# E-inkV0_9.net
KiCad netlist of a schematic drawn in EAGLE
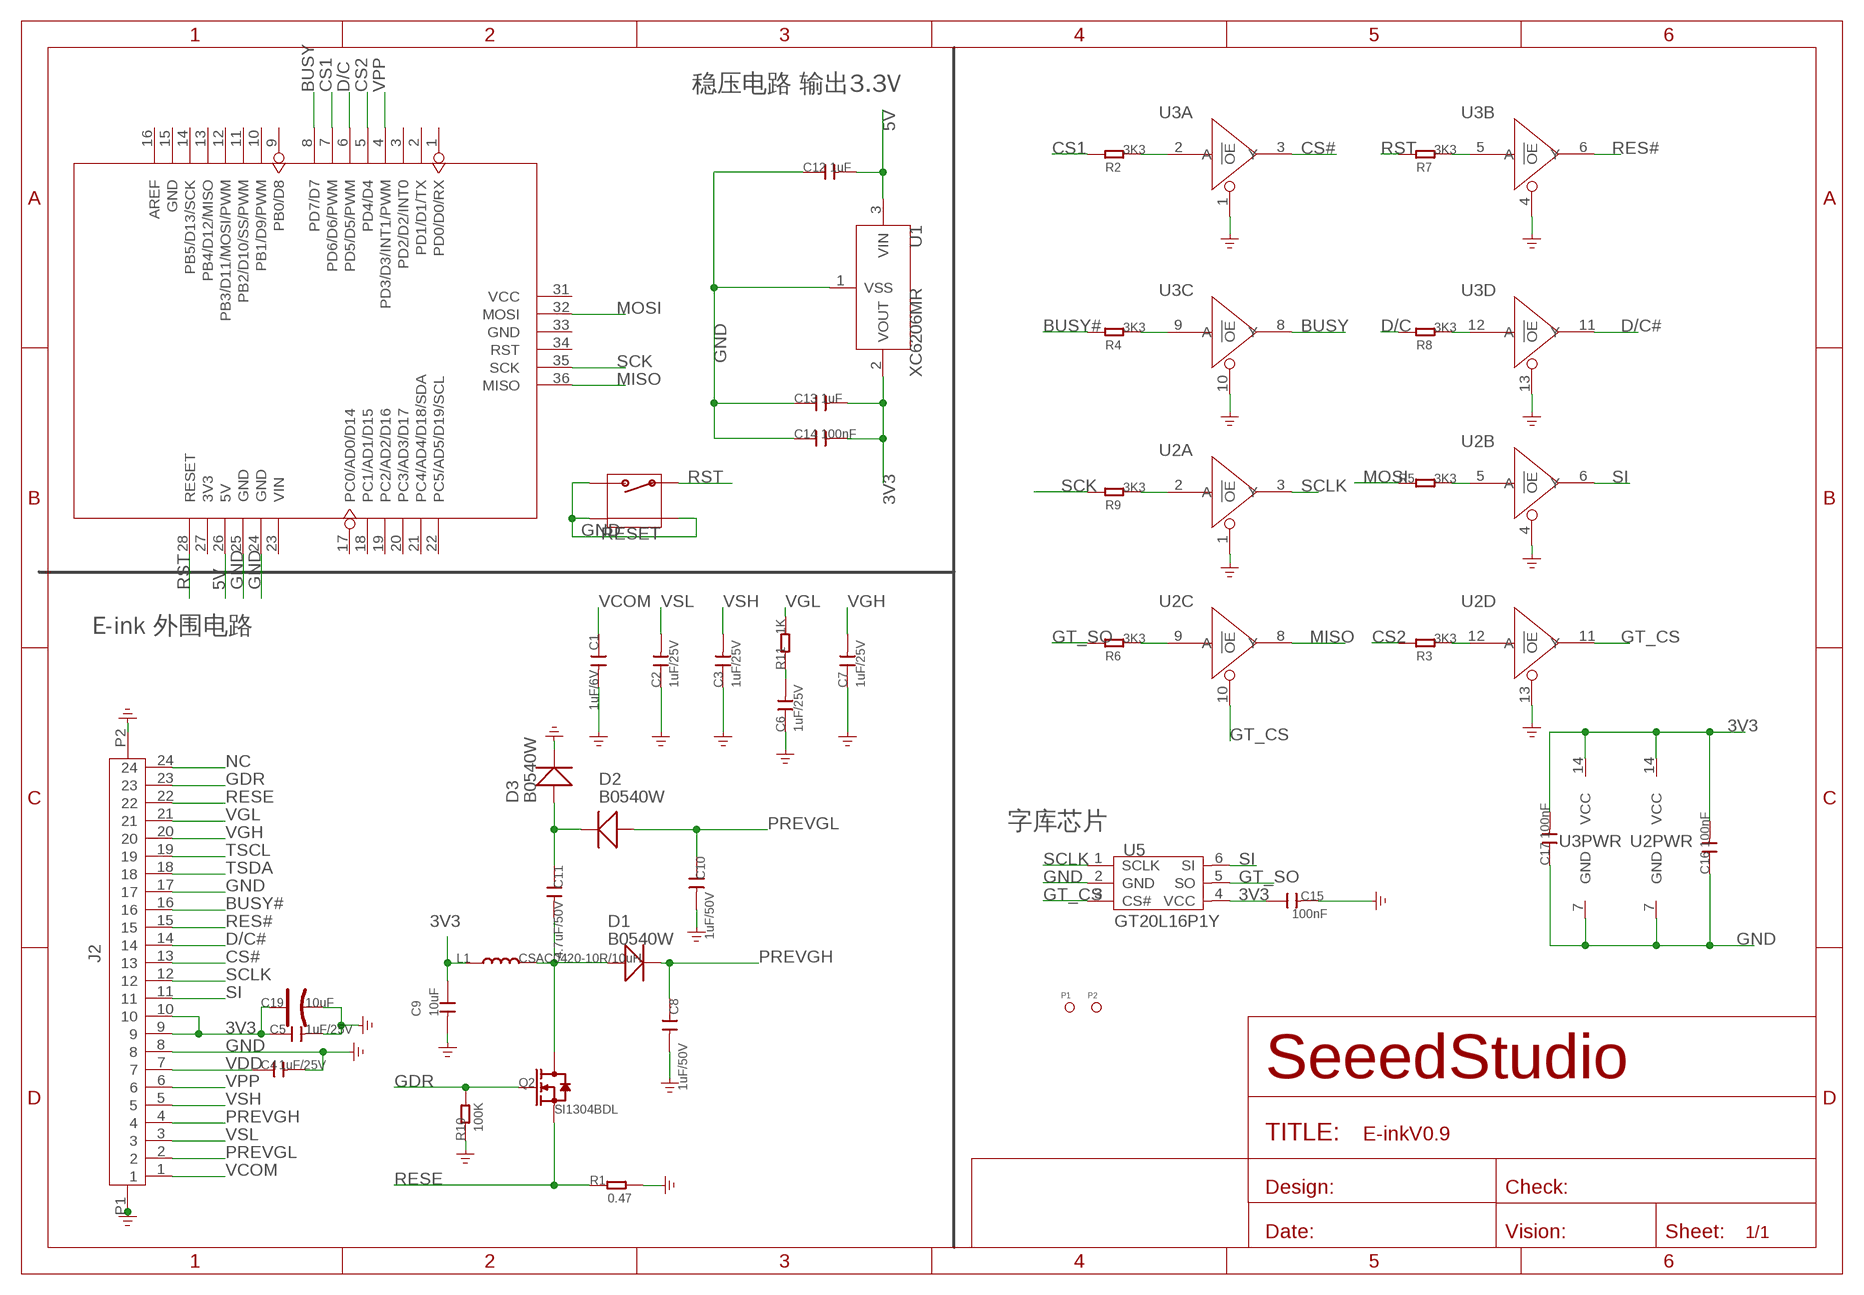
[diagram p0: schematic, sheet 1]

(export (version "E")
  (design (tool "Eeschema 10.0.6"))
  (components
    (comp (ref "C1")
      (value "1uF/6V")
      (footprint "eagle-import:C0805")
      (libsource (lib "eagle-import") (part "C-0805"))
    )
    (comp (ref "C2")
      (value "1uF/25V")
      (footprint "eagle-import:C0805")
      (libsource (lib "eagle-import") (part "C-0805"))
    )
    (comp (ref "C3")
      (value "1uF/25V")
      (footprint "eagle-import:C0805")
      (libsource (lib "eagle-import") (part "C-0805"))
    )
    (comp (ref "C4")
      (value "1uF/25V")
      (footprint "eagle-import:C0805")
      (libsource (lib "eagle-import") (part "C-0805"))
    )
    (comp (ref "C5")
      (value "1uF/25V")
      (footprint "eagle-import:C0805")
      (libsource (lib "eagle-import") (part "C-0805"))
    )
    (comp (ref "C6")
      (value "1uF/25V")
      (footprint "eagle-import:C0805")
      (libsource (lib "eagle-import") (part "C-0805"))
    )
    (comp (ref "C7")
      (value "1uF/25V")
      (footprint "eagle-import:C0805")
      (libsource (lib "eagle-import") (part "C-0805"))
    )
    (comp (ref "C8")
      (value "1uF/50V")
      (footprint "eagle-import:C0805")
      (libsource (lib "eagle-import") (part "C-0805"))
    )
    (comp (ref "C9")
      (value "10uF")
      (footprint "eagle-import:C0805")
      (libsource (lib "eagle-import") (part "C-0805"))
    )
    (comp (ref "C10")
      (value "1uF/50V")
      (footprint "eagle-import:C0805")
      (libsource (lib "eagle-import") (part "C-0805"))
    )
    (comp (ref "C11")
      (value "4.7uF/50V")
      (footprint "eagle-import:C0805")
      (libsource (lib "eagle-import") (part "C-0805"))
    )
    (comp (ref "C12")
      (value "1uF")
      (footprint "eagle-import:C0805")
      (libsource (lib "eagle-import") (part "C-0805"))
    )
    (comp (ref "C13")
      (value "1uF")
      (footprint "eagle-import:C0805")
      (libsource (lib "eagle-import") (part "C-0805"))
    )
    (comp (ref "C14")
      (value "100nF")
      (footprint "eagle-import:C0603")
      (libsource (lib "eagle-import") (part "C-0603"))
    )
    (comp (ref "C15")
      (value "100nF")
      (footprint "eagle-import:C0603")
      (libsource (lib "eagle-import") (part "C-0603"))
    )
    (comp (ref "C16")
      (value "100nF")
      (footprint "eagle-import:C0603")
      (libsource (lib "eagle-import") (part "C-0603"))
    )
    (comp (ref "C17")
      (value "100nF")
      (footprint "eagle-import:C0603")
      (libsource (lib "eagle-import") (part "C-0603"))
    )
    (comp (ref "C19")
      (value "10uF")
      (footprint "eagle-import:AVX-A")
      (libsource (lib "eagle-import") (part "CAP-AVX-A"))
    )
    (comp (ref "D1")
      (value "B0540W")
      (footprint "eagle-import:SOD123-2.7X1.6")
      (libsource (lib "eagle-import") (part "D'MBR0520LT1'"))
    )
    (comp (ref "D2")
      (value "B0540W")
      (footprint "eagle-import:SOD123-2.7X1.6")
      (libsource (lib "eagle-import") (part "D'MBR0520LT1'"))
    )
    (comp (ref "D3")
      (value "B0540W")
      (footprint "eagle-import:SOD123-2.7X1.6")
      (libsource (lib "eagle-import") (part "D'MBR0520LT1'"))
    )
    (comp (ref "J2")
      (value "FPC_CONNECTOR")
      (footprint "eagle-import:24P-0.5")
      (libsource (lib "eagle-import") (part "FPC-CONNECTOR-24P-0.5'ST-FPC-052024-B'"))
    )
    (comp (ref "L1")
      (value "CSAC0420-10R/10uH")
      (footprint "eagle-import:1616BZ")
      (libsource (lib "eagle-import") (part "L'1616BZ'"))
    )
    (comp (ref "P1")
      (value "PAD-MARK")
      (footprint "eagle-import:ROUND-MARK-1.0")
      (fields (field (name "PARTNO") "DNP"))
      (libsource (lib "eagle-import") (part "PAD-MARK"))
    )
    (comp (ref "P2")
      (value "PAD-MARK")
      (footprint "eagle-import:ROUND-MARK-1.0")
      (fields (field (name "PARTNO") "DNP"))
      (libsource (lib "eagle-import") (part "PAD-MARK"))
    )
    (comp (ref "Q2")
      (value "SI1304BDL")
      (footprint "eagle-import:SOT323")
      (libsource (lib "eagle-import") (part "MOSFET-N'SI1304BDL'"))
    )
    (comp (ref "R1")
      (value "0.47")
      (footprint "eagle-import:R0603")
      (libsource (lib "eagle-import") (part "R-0603"))
    )
    (comp (ref "R2")
      (value "3K3")
      (footprint "eagle-import:R0603")
      (libsource (lib "eagle-import") (part "R-0603"))
    )
    (comp (ref "R3")
      (value "3K3")
      (footprint "eagle-import:R0603")
      (libsource (lib "eagle-import") (part "R-0603"))
    )
    (comp (ref "R4")
      (value "3K3")
      (footprint "eagle-import:R0603")
      (libsource (lib "eagle-import") (part "R-0603"))
    )
    (comp (ref "R5")
      (value "3K3")
      (footprint "eagle-import:R0603")
      (libsource (lib "eagle-import") (part "R-0603"))
    )
    (comp (ref "R6")
      (value "3K3")
      (footprint "eagle-import:R0603")
      (libsource (lib "eagle-import") (part "R-0603"))
    )
    (comp (ref "R7")
      (value "3K3")
      (footprint "eagle-import:R0603")
      (libsource (lib "eagle-import") (part "R-0603"))
    )
    (comp (ref "R8")
      (value "3K3")
      (footprint "eagle-import:R0603")
      (libsource (lib "eagle-import") (part "R-0603"))
    )
    (comp (ref "R9")
      (value "3K3")
      (footprint "eagle-import:R0603")
      (libsource (lib "eagle-import") (part "R-0603"))
    )
    (comp (ref "R10")
      (value "100K")
      (footprint "eagle-import:R0603")
      (libsource (lib "eagle-import") (part "R-0603"))
    )
    (comp (ref "R11")
      (value "1K")
      (footprint "eagle-import:R0603")
      (libsource (lib "eagle-import") (part "R-0603"))
    )
    (comp (ref "RESET")
      (value "FOR_TEST_ALBERT_V6_BUTTON_4P_SMD")
      (footprint "eagle-import:FOR_TEST_ALBERT_V6_4P-SMD-7X3.5X3.5")
      (libsource (lib "eagle-import") (part "FOR_TEST_ALBERT_V6_BUTTON_4P_SMD"))
    )
    (comp (ref "U1")
      (value "XC6206MR")
      (footprint "eagle-import:SOT23")
      (libsource (lib "eagle-import") (part "XC6206MR"))
    )
    (comp (ref "U2")
      (value "74VHC125PW")
      (footprint "eagle-import:TSSOP14")
      (libsource (lib "eagle-import") (part "74V125PWHC"))
    )
    (comp (ref "U3")
      (value "74VHC125PW")
      (footprint "eagle-import:TSSOP14")
      (libsource (lib "eagle-import") (part "74V125PWHC"))
    )
    (comp (ref "U4")
      (value "ARDUINO")
      (footprint "eagle-import:ARDUINO-ISP-SMD")
      (libsource (lib "eagle-import") (part "ARDUINO"))
    )
    (comp (ref "U5")
      (value "GT20L16P1Y")
      (footprint "eagle-import:SOT23-6")
      (libsource (lib "eagle-import") (part "GT20L16P1Y"))
    )
  )
  (nets
    (net (code "1") (name "/3V3") (class "Default")
      (node (ref "C13") (pin "2") (pinfunction "2_2") (pintype "passive"))
      (node (ref "C14") (pin "2") (pinfunction "2_2") (pintype "passive"))
      (node (ref "C15") (pin "1") (pinfunction "1_1") (pintype "passive"))
      (node (ref "C16") (pin "2") (pinfunction "2_2") (pintype "passive"))
      (node (ref "C17") (pin "2") (pinfunction "2_2") (pintype "passive"))
      (node (ref "C19") (pin "+") (pinfunction "+_+") (pintype "passive"))
      (node (ref "C5") (pin "1") (pinfunction "1_1") (pintype "passive"))
      (node (ref "C9") (pin "1") (pinfunction "1_1") (pintype "passive"))
      (node (ref "J2") (pin "10") (pinfunction "10_10") (pintype "bidirectional"))
      (node (ref "J2") (pin "9") (pinfunction "9_9") (pintype "bidirectional"))
      (node (ref "L1") (pin "1") (pinfunction "1_1") (pintype "passive"))
      (node (ref "U1") (pin "2") (pinfunction "VOUT_2") (pintype "output"))
      (node (ref "U2") (pin "14") (pinfunction "VCC_14") (pintype "power_in"))
      (node (ref "U3") (pin "14") (pinfunction "VCC_14") (pintype "power_in"))
      (node (ref "U5") (pin "4") (pinfunction "VCC_4") (pintype "power_in"))
    )
    (net (code "2") (name "/5V") (class "Default")
      (node (ref "C12") (pin "2") (pinfunction "2_2") (pintype "passive"))
      (node (ref "U1") (pin "3") (pinfunction "VIN_3") (pintype "input"))
      (node (ref "U4") (pin "26") (pinfunction "5V_26") (pintype "bidirectional"))
    )
    (net (code "3") (name "/BUSY") (class "Default")
      (node (ref "U3") (pin "8") (pinfunction "Y_8") (pintype "bidirectional"))
      (node (ref "U4") (pin "8") (pinfunction "PD7/D7_8") (pintype "bidirectional"))
    )
    (net (code "4") (name "/BUSY#") (class "Default")
      (node (ref "J2") (pin "16") (pinfunction "16_16") (pintype "bidirectional"))
      (node (ref "R4") (pin "1") (pinfunction "1_1") (pintype "passive"))
    )
    (net (code "5") (name "/CS#") (class "Default")
      (node (ref "J2") (pin "13") (pinfunction "13_13") (pintype "bidirectional"))
      (node (ref "U3") (pin "3") (pinfunction "Y_3") (pintype "bidirectional"))
    )
    (net (code "6") (name "/CS1") (class "Default")
      (node (ref "R2") (pin "1") (pinfunction "1_1") (pintype "passive"))
      (node (ref "U4") (pin "7") (pinfunction "PD6/D6/PWM_7") (pintype "bidirectional"))
    )
    (net (code "7") (name "/CS2") (class "Default")
      (node (ref "R3") (pin "1") (pinfunction "1_1") (pintype "passive"))
      (node (ref "U4") (pin "5") (pinfunction "PD4/D4_5") (pintype "bidirectional"))
    )
    (net (code "8") (name "/D{slash}C") (class "Default")
      (node (ref "R8") (pin "1") (pinfunction "1_1") (pintype "passive"))
      (node (ref "U4") (pin "6") (pinfunction "PD5/D5/PWM_6") (pintype "bidirectional"))
    )
    (net (code "9") (name "/D{slash}C#") (class "Default")
      (node (ref "J2") (pin "14") (pinfunction "14_14") (pintype "bidirectional"))
      (node (ref "U3") (pin "11") (pinfunction "Y_11") (pintype "bidirectional"))
    )
    (net (code "10") (name "/GDR") (class "Default")
      (node (ref "J2") (pin "23") (pinfunction "23_23") (pintype "bidirectional"))
      (node (ref "Q2") (pin "1") (pinfunction "G_1") (pintype "passive"))
      (node (ref "R10") (pin "2") (pinfunction "2_2") (pintype "passive"))
    )
    (net (code "11") (name "/GT_CS") (class "Default")
      (node (ref "U2") (pin "10") (pinfunction "~{OE}_10") (pintype "bidirectional"))
      (node (ref "U2") (pin "11") (pinfunction "Y_11") (pintype "bidirectional"))
      (node (ref "U5") (pin "3") (pinfunction "CS#_3") (pintype "input"))
    )
    (net (code "12") (name "/GT_SO") (class "Default")
      (node (ref "R6") (pin "1") (pinfunction "1_1") (pintype "passive"))
      (node (ref "U5") (pin "5") (pinfunction "SO_5") (pintype "output"))
    )
    (net (code "13") (name "/MISO") (class "Default")
      (node (ref "U2") (pin "8") (pinfunction "Y_8") (pintype "bidirectional"))
      (node (ref "U4") (pin "36") (pinfunction "MISO_36") (pintype "bidirectional"))
    )
    (net (code "14") (name "/MOSI") (class "Default")
      (node (ref "R5") (pin "1") (pinfunction "1_1") (pintype "passive"))
      (node (ref "U4") (pin "32") (pinfunction "MOSI_32") (pintype "bidirectional"))
    )
    (net (code "15") (name "/NC") (class "Default")
      (node (ref "J2") (pin "24") (pinfunction "24_24") (pintype "bidirectional"))
    )
    (net (code "16") (name "/PREVGH") (class "Default")
      (node (ref "C8") (pin "1") (pinfunction "1_1") (pintype "passive"))
      (node (ref "D1") (pin "2") (pinfunction "-_2") (pintype "passive"))
      (node (ref "J2") (pin "4") (pinfunction "4_4") (pintype "bidirectional"))
    )
    (net (code "17") (name "/PREVGL") (class "Default")
      (node (ref "C10") (pin "1") (pinfunction "1_1") (pintype "passive"))
      (node (ref "D2") (pin "1") (pinfunction "+_1") (pintype "passive"))
      (node (ref "J2") (pin "2") (pinfunction "2_2") (pintype "bidirectional"))
    )
    (net (code "18") (name "/RES#") (class "Default")
      (node (ref "J2") (pin "15") (pinfunction "15_15") (pintype "bidirectional"))
      (node (ref "U3") (pin "6") (pinfunction "Y_6") (pintype "bidirectional"))
    )
    (net (code "19") (name "/RESE") (class "Default")
      (node (ref "J2") (pin "22") (pinfunction "22_22") (pintype "bidirectional"))
      (node (ref "Q2") (pin "2") (pinfunction "S_2") (pintype "passive"))
      (node (ref "R1") (pin "1") (pinfunction "1_1") (pintype "passive"))
    )
    (net (code "20") (name "/RST") (class "Default")
      (node (ref "R7") (pin "1") (pinfunction "1_1") (pintype "passive"))
      (node (ref "RESET") (pin "1") (pinfunction "1_1") (pintype "bidirectional"))
      (node (ref "U4") (pin "28") (pinfunction "RESET_28") (pintype "bidirectional"))
    )
    (net (code "21") (name "/SCK") (class "Default")
      (node (ref "R9") (pin "1") (pinfunction "1_1") (pintype "passive"))
      (node (ref "U4") (pin "35") (pinfunction "SCK_35") (pintype "bidirectional"))
    )
    (net (code "22") (name "/SCLK") (class "Default")
      (node (ref "J2") (pin "12") (pinfunction "12_12") (pintype "bidirectional"))
      (node (ref "U2") (pin "3") (pinfunction "Y_3") (pintype "bidirectional"))
      (node (ref "U5") (pin "1") (pinfunction "SCLK_1") (pintype "input"))
    )
    (net (code "23") (name "/SI") (class "Default")
      (node (ref "J2") (pin "11") (pinfunction "11_11") (pintype "bidirectional"))
      (node (ref "U2") (pin "6") (pinfunction "Y_6") (pintype "bidirectional"))
      (node (ref "U5") (pin "6") (pinfunction "SI_6") (pintype "input"))
    )
    (net (code "24") (name "/TSCL") (class "Default")
      (node (ref "J2") (pin "19") (pinfunction "19_19") (pintype "bidirectional"))
    )
    (net (code "25") (name "/TSDA") (class "Default")
      (node (ref "J2") (pin "18") (pinfunction "18_18") (pintype "bidirectional"))
    )
    (net (code "26") (name "/VCOM") (class "Default")
      (node (ref "C1") (pin "1") (pinfunction "1_1") (pintype "passive"))
      (node (ref "J2") (pin "1") (pinfunction "1_1") (pintype "bidirectional"))
    )
    (net (code "27") (name "/VDD") (class "Default")
      (node (ref "C4") (pin "1") (pinfunction "1_1") (pintype "passive"))
      (node (ref "J2") (pin "7") (pinfunction "7_7") (pintype "bidirectional"))
    )
    (net (code "28") (name "/VGH") (class "Default")
      (node (ref "C7") (pin "2") (pinfunction "2_2") (pintype "passive"))
      (node (ref "J2") (pin "20") (pinfunction "20_20") (pintype "bidirectional"))
    )
    (net (code "29") (name "/VGL") (class "Default")
      (node (ref "J2") (pin "21") (pinfunction "21_21") (pintype "bidirectional"))
      (node (ref "R11") (pin "2") (pinfunction "2_2") (pintype "passive"))
    )
    (net (code "30") (name "/VPP") (class "Default")
      (node (ref "J2") (pin "6") (pinfunction "6_6") (pintype "bidirectional"))
      (node (ref "U4") (pin "4") (pinfunction "PD3/D3/INT1/PWM_4") (pintype "bidirectional"))
    )
    (net (code "31") (name "/VSH") (class "Default")
      (node (ref "C3") (pin "2") (pinfunction "2_2") (pintype "passive"))
      (node (ref "J2") (pin "5") (pinfunction "5_5") (pintype "bidirectional"))
    )
    (net (code "32") (name "/VSL") (class "Default")
      (node (ref "C2") (pin "2") (pinfunction "2_2") (pintype "passive"))
      (node (ref "J2") (pin "3") (pinfunction "3_3") (pintype "bidirectional"))
    )
    (net (code "33") (name "GND_POWER") (class "Default")
      (node (ref "C1") (pin "2") (pinfunction "2_2") (pintype "passive"))
      (node (ref "C10") (pin "2") (pinfunction "2_2") (pintype "passive"))
      (node (ref "C12") (pin "1") (pinfunction "1_1") (pintype "passive"))
      (node (ref "C13") (pin "1") (pinfunction "1_1") (pintype "passive"))
      (node (ref "C14") (pin "1") (pinfunction "1_1") (pintype "passive"))
      (node (ref "C15") (pin "2") (pinfunction "2_2") (pintype "passive"))
      (node (ref "C16") (pin "1") (pinfunction "1_1") (pintype "passive"))
      (node (ref "C17") (pin "1") (pinfunction "1_1") (pintype "passive"))
      (node (ref "C19") (pin "-") (pinfunction "-_-") (pintype "passive"))
      (node (ref "C2") (pin "1") (pinfunction "1_1") (pintype "passive"))
      (node (ref "C3") (pin "1") (pinfunction "1_1") (pintype "passive"))
      (node (ref "C4") (pin "2") (pinfunction "2_2") (pintype "passive"))
      (node (ref "C5") (pin "2") (pinfunction "2_2") (pintype "passive"))
      (node (ref "C6") (pin "1") (pinfunction "1_1") (pintype "passive"))
      (node (ref "C7") (pin "1") (pinfunction "1_1") (pintype "passive"))
      (node (ref "C8") (pin "2") (pinfunction "2_2") (pintype "passive"))
      (node (ref "C9") (pin "2") (pinfunction "2_2") (pintype "passive"))
      (node (ref "D3") (pin "2") (pinfunction "-_2") (pintype "passive"))
      (node (ref "J2") (pin "17") (pinfunction "17_17") (pintype "bidirectional"))
      (node (ref "J2") (pin "8") (pinfunction "8_8") (pintype "bidirectional"))
      (node (ref "J2") (pin "P1") (pinfunction "P1_P1") (pintype "bidirectional"))
      (node (ref "J2") (pin "P2") (pinfunction "P2_P2") (pintype "bidirectional"))
      (node (ref "R1") (pin "2") (pinfunction "2_2") (pintype "passive"))
      (node (ref "R10") (pin "1") (pinfunction "1_1") (pintype "passive"))
      (node (ref "RESET") (pin "2") (pinfunction "2_2") (pintype "bidirectional"))
      (node (ref "RESET") (pin "S1") (pinfunction "S1_S1") (pintype "bidirectional"))
      (node (ref "RESET") (pin "S2") (pinfunction "S2_S2") (pintype "bidirectional"))
      (node (ref "U1") (pin "1") (pinfunction "VSS_1") (pintype "power_in"))
      (node (ref "U2") (pin "1") (pinfunction "~{OE}_1") (pintype "bidirectional"))
      (node (ref "U2") (pin "13") (pinfunction "~{OE}_13") (pintype "bidirectional"))
      (node (ref "U2") (pin "4") (pinfunction "~{OE}_4") (pintype "bidirectional"))
      (node (ref "U2") (pin "7") (pinfunction "GND_7") (pintype "power_in"))
      (node (ref "U3") (pin "1") (pinfunction "~{OE}_1") (pintype "bidirectional"))
      (node (ref "U3") (pin "10") (pinfunction "~{OE}_10") (pintype "bidirectional"))
      (node (ref "U3") (pin "13") (pinfunction "~{OE}_13") (pintype "bidirectional"))
      (node (ref "U3") (pin "4") (pinfunction "~{OE}_4") (pintype "bidirectional"))
      (node (ref "U3") (pin "7") (pinfunction "GND_7") (pintype "power_in"))
      (node (ref "U4") (pin "24") (pinfunction "GND_24") (pintype "bidirectional"))
      (node (ref "U4") (pin "25") (pinfunction "GND_25") (pintype "bidirectional"))
      (node (ref "U5") (pin "2") (pinfunction "GND_2") (pintype "power_in"))
    )
    (net (code "34") (name "Net-(C6-Pad2)") (class "Default")
      (node (ref "C6") (pin "2") (pinfunction "2_2") (pintype "passive"))
      (node (ref "R11") (pin "1") (pinfunction "1_1") (pintype "passive"))
    )
    (net (code "35") (name "Net-(D1-+)") (class "Default")
      (node (ref "C11") (pin "2") (pinfunction "2_2") (pintype "passive"))
      (node (ref "D1") (pin "1") (pinfunction "+_1") (pintype "passive"))
      (node (ref "L1") (pin "2") (pinfunction "2_2") (pintype "passive"))
      (node (ref "Q2") (pin "3") (pinfunction "D_3") (pintype "passive"))
    )
    (net (code "36") (name "Net-(D2--)") (class "Default")
      (node (ref "C11") (pin "1") (pinfunction "1_1") (pintype "passive"))
      (node (ref "D2") (pin "2") (pinfunction "-_2") (pintype "passive"))
      (node (ref "D3") (pin "1") (pinfunction "+_1") (pintype "passive"))
    )
    (net (code "37") (name "Net-(U2A-A)") (class "Default")
      (node (ref "R9") (pin "2") (pinfunction "2_2") (pintype "passive"))
      (node (ref "U2") (pin "2") (pinfunction "A_2") (pintype "bidirectional"))
    )
    (net (code "38") (name "Net-(U2B-A)") (class "Default")
      (node (ref "R5") (pin "2") (pinfunction "2_2") (pintype "passive"))
      (node (ref "U2") (pin "5") (pinfunction "A_5") (pintype "bidirectional"))
    )
    (net (code "39") (name "Net-(U2C-A)") (class "Default")
      (node (ref "R6") (pin "2") (pinfunction "2_2") (pintype "passive"))
      (node (ref "U2") (pin "9") (pinfunction "A_9") (pintype "bidirectional"))
    )
    (net (code "40") (name "Net-(U2D-A)") (class "Default")
      (node (ref "R3") (pin "2") (pinfunction "2_2") (pintype "passive"))
      (node (ref "U2") (pin "12") (pinfunction "A_12") (pintype "bidirectional"))
    )
    (net (code "41") (name "Net-(U3A-A)") (class "Default")
      (node (ref "R2") (pin "2") (pinfunction "2_2") (pintype "passive"))
      (node (ref "U3") (pin "2") (pinfunction "A_2") (pintype "bidirectional"))
    )
    (net (code "42") (name "Net-(U3B-A)") (class "Default")
      (node (ref "R7") (pin "2") (pinfunction "2_2") (pintype "passive"))
      (node (ref "U3") (pin "5") (pinfunction "A_5") (pintype "bidirectional"))
    )
    (net (code "43") (name "Net-(U3C-A)") (class "Default")
      (node (ref "R4") (pin "2") (pinfunction "2_2") (pintype "passive"))
      (node (ref "U3") (pin "9") (pinfunction "A_9") (pintype "bidirectional"))
    )
    (net (code "44") (name "Net-(U3D-A)") (class "Default")
      (node (ref "R8") (pin "2") (pinfunction "2_2") (pintype "passive"))
      (node (ref "U3") (pin "12") (pinfunction "A_12") (pintype "bidirectional"))
    )
    (net (code "45") (name "unconnected-(U4-3V3-Pad27)") (class "Default")
      (node (ref "U4") (pin "27") (pinfunction "3V3_27") (pintype "bidirectional"))
    )
    (net (code "46") (name "unconnected-(U4-AREF-Pad16)") (class "Default")
      (node (ref "U4") (pin "16") (pinfunction "AREF_16") (pintype "bidirectional"))
    )
    (net (code "47") (name "unconnected-(U4-GND-Pad15)") (class "Default")
      (node (ref "U4") (pin "15") (pinfunction "GND_15") (pintype "bidirectional"))
    )
    (net (code "48") (name "unconnected-(U4-GND-Pad33)") (class "Default")
      (node (ref "U4") (pin "33") (pinfunction "GND_33") (pintype "bidirectional"))
    )
    (net (code "49") (name "unconnected-(U4-PB0{slash}D8-Pad9)") (class "Default")
      (node (ref "U4") (pin "9") (pinfunction "PB0/D8_9") (pintype "bidirectional"))
    )
    (net (code "50") (name "unconnected-(U4-PB1{slash}D9{slash}PWM-Pad10)") (class "Default")
      (node (ref "U4") (pin "10") (pinfunction "PB1/D9/PWM_10") (pintype "bidirectional"))
    )
    (net (code "51") (name "unconnected-(U4-PB2{slash}D10{slash}SS{slash}PWM-Pad11)") (class "Default")
      (node (ref "U4") (pin "11") (pinfunction "PB2/D10/SS/PWM_11") (pintype "bidirectional"))
    )
    (net (code "52") (name "unconnected-(U4-PB3{slash}D11{slash}MOSI{slash}PWM-Pad12)") (class "Default")
      (node (ref "U4") (pin "12") (pinfunction "PB3/D11/MOSI/PWM_12") (pintype "bidirectional"))
    )
    (net (code "53") (name "unconnected-(U4-PB4{slash}D12{slash}MISO-Pad13)") (class "Default")
      (node (ref "U4") (pin "13") (pinfunction "PB4/D12/MISO_13") (pintype "bidirectional"))
    )
    (net (code "54") (name "unconnected-(U4-PB5{slash}D13{slash}SCK-Pad14)") (class "Default")
      (node (ref "U4") (pin "14") (pinfunction "PB5/D13/SCK_14") (pintype "bidirectional"))
    )
    (net (code "55") (name "unconnected-(U4-PC0{slash}AD0{slash}D14-Pad17)") (class "Default")
      (node (ref "U4") (pin "17") (pinfunction "PC0/AD0/D14_17") (pintype "bidirectional"))
    )
    (net (code "56") (name "unconnected-(U4-PC1{slash}AD1{slash}D15-Pad18)") (class "Default")
      (node (ref "U4") (pin "18") (pinfunction "PC1/AD1/D15_18") (pintype "bidirectional"))
    )
    (net (code "57") (name "unconnected-(U4-PC2{slash}AD2{slash}D16-Pad19)") (class "Default")
      (node (ref "U4") (pin "19") (pinfunction "PC2/AD2/D16_19") (pintype "bidirectional"))
    )
    (net (code "58") (name "unconnected-(U4-PC3{slash}AD3{slash}D17-Pad20)") (class "Default")
      (node (ref "U4") (pin "20") (pinfunction "PC3/AD3/D17_20") (pintype "bidirectional"))
    )
    (net (code "59") (name "unconnected-(U4-PC4{slash}AD4{slash}D18{slash}SDA-Pad21)") (class "Default")
      (node (ref "U4") (pin "21") (pinfunction "PC4/AD4/D18/SDA_21") (pintype "bidirectional"))
    )
    (net (code "60") (name "unconnected-(U4-PC5{slash}AD5{slash}D19{slash}SCL-Pad22)") (class "Default")
      (node (ref "U4") (pin "22") (pinfunction "PC5/AD5/D19/SCL_22") (pintype "bidirectional"))
    )
    (net (code "61") (name "unconnected-(U4-PD0{slash}D0{slash}RX-Pad1)") (class "Default")
      (node (ref "U4") (pin "1") (pinfunction "PD0/D0/RX_1") (pintype "bidirectional"))
    )
    (net (code "62") (name "unconnected-(U4-PD1{slash}D1{slash}TX-Pad2)") (class "Default")
      (node (ref "U4") (pin "2") (pinfunction "PD1/D1/TX_2") (pintype "bidirectional"))
    )
    (net (code "63") (name "unconnected-(U4-PD2{slash}D2{slash}INT0-Pad3)") (class "Default")
      (node (ref "U4") (pin "3") (pinfunction "PD2/D2/INT0_3") (pintype "bidirectional"))
    )
    (net (code "64") (name "unconnected-(U4-RST-Pad34)") (class "Default")
      (node (ref "U4") (pin "34") (pinfunction "RST_34") (pintype "bidirectional"))
    )
    (net (code "65") (name "unconnected-(U4-VCC-Pad31)") (class "Default")
      (node (ref "U4") (pin "31") (pinfunction "VCC_31") (pintype "bidirectional"))
    )
    (net (code "66") (name "unconnected-(U4-VIN-Pad23)") (class "Default")
      (node (ref "U4") (pin "23") (pinfunction "VIN_23") (pintype "bidirectional"))
    )
  )
)
